# Processor.net
KiCad netlist of a schematic drawn in Altium Designer
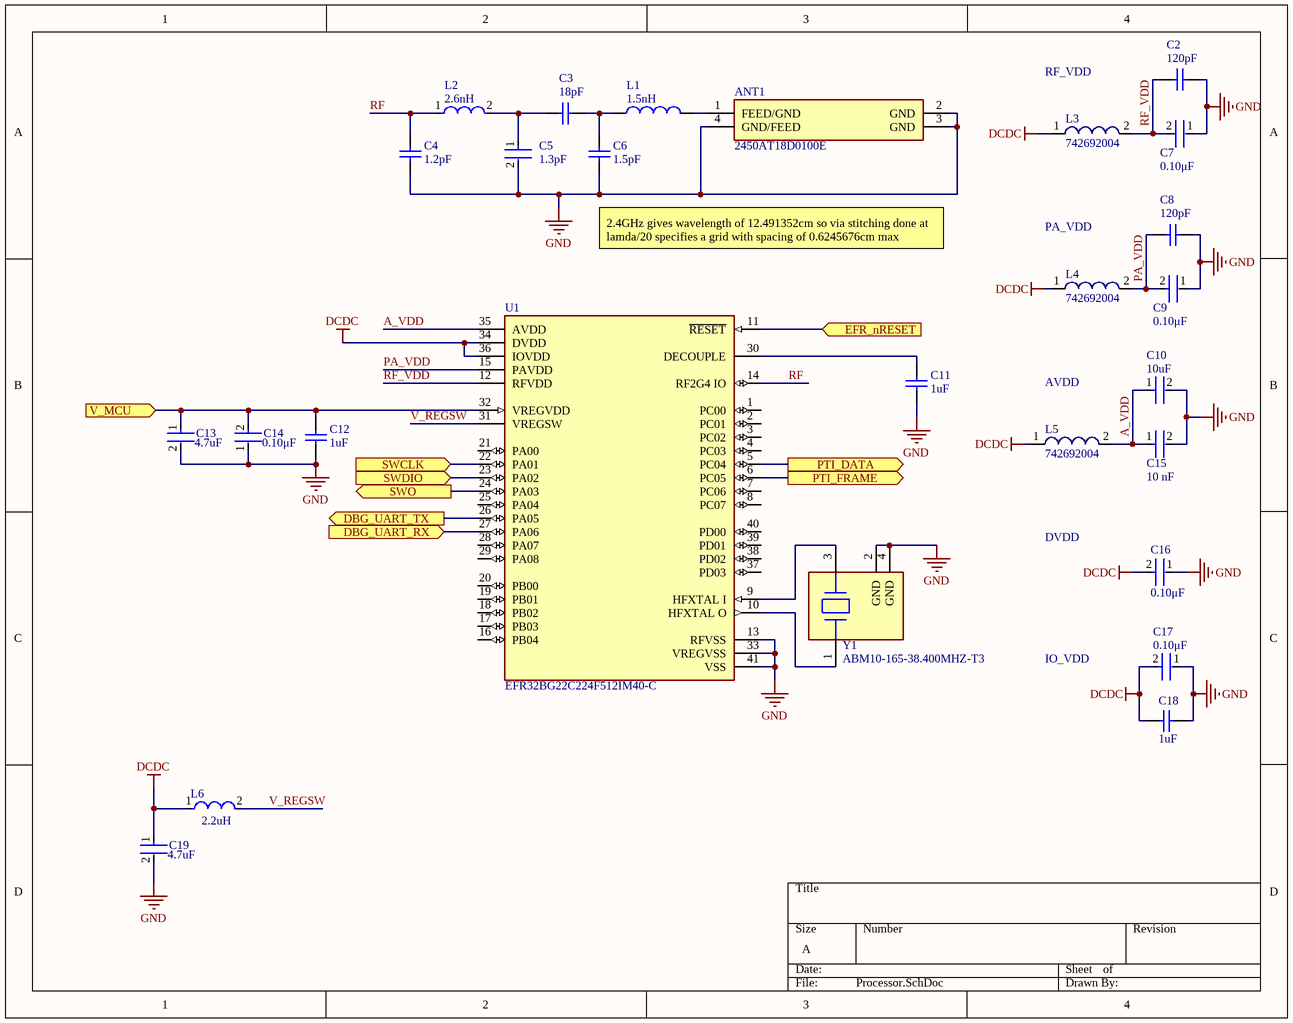
[diagram p0: Processor.SchDoc]

(export (version "E")
  (design (tool "Eeschema 10.0.6"))
  (components
    (comp (ref "ANT1")
      (value "2450AT18D0100E")
      (footprint "FP-2450AT18D0100E-MFG")
      (description "RF ANT 2.4GHZ CHIP SOLDER SMD")
      (libsource (lib "Altium Content Vault") (part "2754107183b9f3d7969499aeff111fc"))
    )
    (comp (ref "C2")
      (value "C0603C121J5GACAUTO")
      (footprint "CAPC1608X87X35LL15T15")
      (fields (field (name "MANUFACTURER") "Kemet") (field (name "CAPACITANCE") "120pF"))
      (libsource (lib "Altium Content Vault") (part "CAP"))
    )
    (comp (ref "C3")
      (value "0402ZK180GBSTR")
      (footprint "CAPC1006X50X20NL10T10")
      (fields (field (name "MANUFACTURER") "AVX Interconnect / Elco") (field (name "CAPACITANCE") "18pF"))
      (libsource (lib "Altium Content Vault") (part "CAP"))
    )
    (comp (ref "C4")
      (value "04023J1R2BBSTR")
      (footprint "CAPC1006X50X20LL10T10")
      (fields (field (name "MANUFACTURER") "AVX Interconnect / Elco") (field (name "CAPACITANCE") "1.2pF"))
      (libsource (lib "Altium Content Vault") (part "CAP"))
    )
    (comp (ref "C5")
      (value "GJM1555C1H1R3BB01D")
      (footprint "FP-GJM155-0_05-MFG")
      (description "Multi-Layer Ceramic Capacitor 1.3pF C0G  ±0.1pF 0402 Paper T/R")
      (fields (field (name "CAPACITANCE") "1.3pF"))
      (libsource (lib "Altium Content Vault") (part "02cd4be3c70576c341d710602a673aa"))
    )
    (comp (ref "C6")
      (value "04023J1R5PBSTR")
      (footprint "CAPC1006X50X20ML10T10")
      (fields (field (name "MANUFACTURER") "AVX Interconnect / Elco") (field (name "CAPACITANCE") "1.5pF"))
      (libsource (lib "Altium Content Vault") (part "CAP"))
    )
    (comp (ref "C7")
      (value "GRM155R71C104KA88D")
      (footprint "FP-GRM15-MFG")
      (description "CAP CER 0.1UF 16V X7R 0402")
      (fields
        (field (name "TOLERANCE") "10%")
        (field (name "OCTOPART") "https://octopart.com/grm155r71c104ka88d-murata-196880")
        (field (name "CAPACITANCE") "0.10μF")
      )
      (libsource (lib "Altium Content Vault") (part "236180d848d6139a670b325ea6854c9"))
    )
    (comp (ref "C8")
      (value "C0603C121J5GACAUTO")
      (footprint "CAPC1608X87X35LL15T15")
      (fields (field (name "MANUFACTURER") "Kemet") (field (name "CAPACITANCE") "120pF"))
      (libsource (lib "Altium Content Vault") (part "CAP"))
    )
    (comp (ref "C9")
      (value "GRM155R71C104KA88D")
      (footprint "FP-GRM15-MFG")
      (description "CAP CER 0.1UF 16V X7R 0402")
      (fields
        (field (name "TOLERANCE") "10%")
        (field (name "OCTOPART") "https://octopart.com/grm155r71c104ka88d-murata-196880")
        (field (name "CAPACITANCE") "0.10μF")
      )
      (libsource (lib "Altium Content Vault") (part "236180d848d6139a670b325ea6854c9"))
    )
    (comp (ref "C10")
      (value "GRM188R60J106ME47D")
      (footprint "FP-GRM188-0_1-e0_2_0_55-IPC_A")
      (description "Chip Multilayer Ceramic Capacitors for General Purpose, 0603, 10uF, X5R, 15%, 20%, 6.3V")
      (fields
        (field (name "CAPACITANCE") "10uF")
        (field (name "VOLTAGE") "6.3V")
        (field (name "TOLERANCE") "20%")
      )
      (libsource (lib "Altium Content Vault") (part "02cd4be3c70576c341d710602a673aa"))
    )
    (comp (ref "C11")
      (value "C0603C105K9PACTU")
      (footprint "CAPC1608X90X35LL15T15")
      (fields (field (name "MANUFACTURER") "Kemet") (field (name "CAPACITANCE") "1uF"))
      (libsource (lib "Altium Content Vault") (part "CAP"))
    )
    (comp (ref "C12")
      (value "C0603C105K9PACTU")
      (footprint "CAPC1608X90X35LL15T15")
      (fields (field (name "MANUFACTURER") "Kemet") (field (name "CAPACITANCE") "1uF"))
      (libsource (lib "Altium Content Vault") (part "CAP"))
    )
    (comp (ref "C13")
      (value "CL10B475KQ8NQNC")
      (footprint "FP-CL10-IPC_C")
      (description "CAP CER 4.7UF 6.3V X7R 0603")
      (fields
        (field (name "TOLERANCE") "10%")
        (field (name "CAPACITANCE") "4.7uF")
        (field (name "OCTOPART") "https://octopart.com/cl10b475kq8nqnc-samsung-24957976")
      )
      (libsource (lib "Altium Content Vault") (part "11868f565c42a9108669ba33697ecf6"))
    )
    (comp (ref "C14")
      (value "GRM155R71C104KA88D")
      (footprint "FP-GRM15-MFG")
      (description "CAP CER 0.1UF 16V X7R 0402")
      (fields
        (field (name "TOLERANCE") "10%")
        (field (name "OCTOPART") "https://octopart.com/grm155r71c104ka88d-murata-196880")
        (field (name "CAPACITANCE") "0.10μF")
      )
      (libsource (lib "Altium Content Vault") (part "236180d848d6139a670b325ea6854c9"))
    )
    (comp (ref "C15")
      (value "CC0603KRX7R9BB103")
      (footprint "FP-CC0603-DA-MFG")
      (description "CAP CER 10000PF 50V X7R 0603")
      (fields
        (field (name "TOLERANCE") "0.1")
        (field (name "MANUFACTURER") "YAGEO")
        (field (name "CAPACITANCE") "10 nF")
      )
      (libsource (lib "Altium Content Vault") (part "11868f565c42a9108669ba33697ecf6"))
    )
    (comp (ref "C16")
      (value "GRM155R71C104KA88D")
      (footprint "FP-GRM15-MFG")
      (description "CAP CER 0.1UF 16V X7R 0402")
      (fields
        (field (name "TOLERANCE") "10%")
        (field (name "OCTOPART") "https://octopart.com/grm155r71c104ka88d-murata-196880")
        (field (name "CAPACITANCE") "0.10μF")
      )
      (libsource (lib "Altium Content Vault") (part "236180d848d6139a670b325ea6854c9"))
    )
    (comp (ref "C17")
      (value "GRM155R71C104KA88D")
      (footprint "FP-GRM15-MFG")
      (description "CAP CER 0.1UF 16V X7R 0402")
      (fields
        (field (name "TOLERANCE") "10%")
        (field (name "OCTOPART") "https://octopart.com/grm155r71c104ka88d-murata-196880")
        (field (name "CAPACITANCE") "0.10μF")
      )
      (libsource (lib "Altium Content Vault") (part "236180d848d6139a670b325ea6854c9"))
    )
    (comp (ref "C18")
      (value "C0603C105K9PACTU")
      (footprint "CAPC1608X90X35LL15T15")
      (fields (field (name "MANUFACTURER") "Kemet") (field (name "CAPACITANCE") "1uF"))
      (libsource (lib "Altium Content Vault") (part "CAP"))
    )
    (comp (ref "C19")
      (value "CL10B475KQ8NQNC")
      (footprint "FP-CL10-IPC_C")
      (description "CAP CER 4.7UF 6.3V X7R 0603")
      (fields
        (field (name "TOLERANCE") "10%")
        (field (name "CAPACITANCE") "4.7uF")
        (field (name "OCTOPART") "https://octopart.com/cl10b475kq8nqnc-samsung-24957976")
      )
      (libsource (lib "Altium Content Vault") (part "11868f565c42a9108669ba33697ecf6"))
    )
    (comp (ref "L1")
      (value "744901015")
      (footprint "WE-TCI_0402")
      (description "744901015 Fixed Ind 1.5NH 700MA 200MOHM Sm")
      (fields (field (name "INDUCTANCE") "1.5nH"))
      (libsource (lib "Altium Content Vault") (part "Inductor - 1"))
    )
    (comp (ref "L2")
      (value "LQW15AN2N6G8ZD")
      (footprint "FP-LQW15AN_80-MFG")
      (description "Wire Wound RF Inductor for Automotive 2.6nH ±2% 1950mA 0.035Ω 0402 (1005)")
      (fields (field (name "INDUCTANCE") "2.6nH"))
      (libsource (lib "Altium Content Vault") (part "725321dda6339637d4d059423bc1c3c"))
    )
    (comp (ref "L3")
      (value "742692004")
      (footprint "WE-TMSB 0201")
      (description "Tiny Multilayer Suppression  Bead  WE-TMSB, Z= 240 Ohm")
      (fields (field (name "MANUFACTURER") "Wuerth Elektronik"))
      (libsource (lib "Altium Content Vault") (part "WE-IND-INDUCTOR-2"))
    )
    (comp (ref "L4")
      (value "742692004")
      (footprint "WE-TMSB 0201")
      (description "Tiny Multilayer Suppression  Bead  WE-TMSB, Z= 240 Ohm")
      (fields (field (name "MANUFACTURER") "Wuerth Elektronik"))
      (libsource (lib "Altium Content Vault") (part "WE-IND-INDUCTOR-2"))
    )
    (comp (ref "L5")
      (value "742692004")
      (footprint "WE-TMSB 0201")
      (description "Tiny Multilayer Suppression  Bead  WE-TMSB, Z= 240 Ohm")
      (fields (field (name "MANUFACTURER") "Wuerth Elektronik"))
      (libsource (lib "Altium Content Vault") (part "WE-IND-INDUCTOR-2"))
    )
    (comp (ref "L6")
      (value "LQM18PZ2R2MFHD")
      (footprint "FP-LQM18PZ_FH-MFG")
      (description "FIXED IND 2.2UH 700MA 470MOHM SM")
      (fields (field (name "TOLERANCE") "20%") (field (name "INDUCTANCE") "2.2uH"))
      (libsource (lib "Altium Content Vault") (part "725321dda6339637d4d059423bc1c3c"))
    )
    (comp (ref "U1")
      (value "EFR32BG22C224F512IM40-C")
      (footprint "FP-EFR32BG22C224F512IM40-IPC_C")
      (description "BLUE GECKO, QFN40, SECURE BOOT W")
      (libsource (lib "Altium Content Vault") (part "033e3ed7e9e35dc86ce331788b84acd"))
    )
    (comp (ref "Y1")
      (value "ABM10-165-38.400MHZ-T3")
      (footprint "FP-ABM10-165-MFG")
      (description "CRYSTAL 38.4000MHZ 10PF SMD")
      (libsource (lib "Altium Content Vault") (part "bb957c91121ec8fefe2b6ffeb011d4b"))
    )
  )
  (nets
    (net (code "1") (name "/A_VDD") (class "Default")
      (node (ref "C10") (pin "1") (pinfunction "1_1") (pintype "passive"))
      (node (ref "C15") (pin "1") (pinfunction "1_1") (pintype "passive"))
      (node (ref "L5") (pin "2") (pinfunction "2_2") (pintype "passive"))
      (node (ref "U1") (pin "35") (pinfunction "AVDD_35") (pintype "power_in"))
    )
    (net (code "2") (name "/DBG_UART_RX") (class "Default")
      (node (ref "U1") (pin "27") (pinfunction "PA06_27") (pintype "bidirectional"))
    )
    (net (code "3") (name "/DBG_UART_TX") (class "Default")
      (node (ref "U1") (pin "26") (pinfunction "PA05_26") (pintype "bidirectional"))
    )
    (net (code "4") (name "/EFR_nRESET") (class "Default")
      (node (ref "U1") (pin "11") (pinfunction "~{RESET}_11") (pintype "input"))
    )
    (net (code "5") (name "/PA_VDD") (class "Default")
      (node (ref "C8") (pin "1") (pinfunction "1_1") (pintype "passive"))
      (node (ref "C9") (pin "2") (pinfunction "2_2") (pintype "passive"))
      (node (ref "L4") (pin "2") (pinfunction "2_2") (pintype "passive"))
      (node (ref "U1") (pin "15") (pinfunction "PAVDD_15") (pintype "power_in"))
    )
    (net (code "6") (name "/PTI_DATA") (class "Default")
      (node (ref "U1") (pin "5") (pinfunction "PC04_5") (pintype "bidirectional"))
    )
    (net (code "7") (name "/PTI_FRAME") (class "Default")
      (node (ref "U1") (pin "6") (pinfunction "PC05_6") (pintype "bidirectional"))
    )
    (net (code "8") (name "/RF") (class "Default")
      (node (ref "C4") (pin "2") (pinfunction "2_2") (pintype "passive"))
      (node (ref "L2") (pin "1") (pinfunction "1_1") (pintype "passive"))
      (node (ref "U1") (pin "14") (pinfunction "RF2G4_IO_14") (pintype "bidirectional"))
    )
    (net (code "9") (name "/RF_VDD") (class "Default")
      (node (ref "C2") (pin "1") (pinfunction "1_1") (pintype "passive"))
      (node (ref "C7") (pin "2") (pinfunction "2_2") (pintype "passive"))
      (node (ref "L3") (pin "2") (pinfunction "2_2") (pintype "passive"))
      (node (ref "U1") (pin "12") (pinfunction "RFVDD_12") (pintype "power_in"))
    )
    (net (code "10") (name "/SWCLK") (class "Default")
      (node (ref "U1") (pin "22") (pinfunction "PA01_22") (pintype "bidirectional"))
    )
    (net (code "11") (name "/SWDIO") (class "Default")
      (node (ref "U1") (pin "23") (pinfunction "PA02_23") (pintype "bidirectional"))
    )
    (net (code "12") (name "/SWO") (class "Default")
      (node (ref "U1") (pin "24") (pinfunction "PA03_24") (pintype "bidirectional"))
    )
    (net (code "13") (name "/V_MCU") (class "Default")
      (node (ref "C12") (pin "2") (pinfunction "2_2") (pintype "passive"))
      (node (ref "C13") (pin "1") (pinfunction "1_1") (pintype "passive"))
      (node (ref "C14") (pin "2") (pinfunction "2_2") (pintype "passive"))
      (node (ref "U1") (pin "32") (pinfunction "VREGVDD_32") (pintype "input"))
    )
    (net (code "14") (name "/V_REGSW") (class "Default")
      (node (ref "L6") (pin "2") (pinfunction "2_2") (pintype "passive"))
      (node (ref "U1") (pin "31") (pinfunction "VREGSW_31") (pintype "power_in"))
    )
    (net (code "15") (name "DCDC") (class "Default")
      (node (ref "C16") (pin "2") (pinfunction "2_2") (pintype "passive"))
      (node (ref "C17") (pin "2") (pinfunction "2_2") (pintype "passive"))
      (node (ref "C18") (pin "2") (pinfunction "2_2") (pintype "passive"))
      (node (ref "C19") (pin "1") (pinfunction "1_1") (pintype "passive"))
      (node (ref "L3") (pin "1") (pinfunction "1_1") (pintype "passive"))
      (node (ref "L4") (pin "1") (pinfunction "1_1") (pintype "passive"))
      (node (ref "L5") (pin "1") (pinfunction "1_1") (pintype "passive"))
      (node (ref "L6") (pin "1") (pinfunction "1_1") (pintype "passive"))
      (node (ref "U1") (pin "34") (pinfunction "DVDD_34") (pintype "power_in"))
      (node (ref "U1") (pin "36") (pinfunction "IOVDD_36") (pintype "power_in"))
    )
    (net (code "16") (name "GND") (class "Default")
      (node (ref "ANT1") (pin "2") (pinfunction "GND_2") (pintype "power_in"))
      (node (ref "ANT1") (pin "3") (pinfunction "GND_3") (pintype "power_in"))
      (node (ref "ANT1") (pin "4") (pinfunction "GND/FEED_4") (pintype "power_in"))
      (node (ref "C10") (pin "2") (pinfunction "2_2") (pintype "passive"))
      (node (ref "C11") (pin "1") (pinfunction "1_1") (pintype "passive"))
      (node (ref "C12") (pin "1") (pinfunction "1_1") (pintype "passive"))
      (node (ref "C13") (pin "2") (pinfunction "2_2") (pintype "passive"))
      (node (ref "C14") (pin "1") (pinfunction "1_1") (pintype "passive"))
      (node (ref "C15") (pin "2") (pinfunction "2_2") (pintype "passive"))
      (node (ref "C16") (pin "1") (pinfunction "1_1") (pintype "passive"))
      (node (ref "C17") (pin "1") (pinfunction "1_1") (pintype "passive"))
      (node (ref "C18") (pin "1") (pinfunction "1_1") (pintype "passive"))
      (node (ref "C19") (pin "2") (pinfunction "2_2") (pintype "passive"))
      (node (ref "C2") (pin "2") (pinfunction "2_2") (pintype "passive"))
      (node (ref "C4") (pin "1") (pinfunction "1_1") (pintype "passive"))
      (node (ref "C5") (pin "2") (pinfunction "2_2") (pintype "passive"))
      (node (ref "C6") (pin "1") (pinfunction "1_1") (pintype "passive"))
      (node (ref "C7") (pin "1") (pinfunction "1_1") (pintype "passive"))
      (node (ref "C8") (pin "2") (pinfunction "2_2") (pintype "passive"))
      (node (ref "C9") (pin "1") (pinfunction "1_1") (pintype "passive"))
      (node (ref "U1") (pin "13") (pinfunction "RFVSS_13") (pintype "power_in"))
      (node (ref "U1") (pin "33") (pinfunction "VREGVSS_33") (pintype "power_in"))
      (node (ref "U1") (pin "41") (pinfunction "VSS_41") (pintype "power_in"))
      (node (ref "Y1") (pin "2") (pinfunction "GND_2") (pintype "power_in"))
      (node (ref "Y1") (pin "4") (pinfunction "GND_4") (pintype "power_in"))
    )
    (net (code "17") (name "Net-(ANT1-FEED{slash}GND)") (class "Default")
      (node (ref "ANT1") (pin "1") (pinfunction "FEED/GND_1") (pintype "power_in"))
      (node (ref "L1") (pin "2") (pinfunction "2_2") (pintype "passive"))
    )
    (net (code "18") (name "Net-(C3-Pad1)") (class "Default")
      (node (ref "C3") (pin "1") (pinfunction "1_1") (pintype "passive"))
      (node (ref "C5") (pin "1") (pinfunction "1_1") (pintype "passive"))
      (node (ref "L2") (pin "2") (pinfunction "2_2") (pintype "passive"))
    )
    (net (code "19") (name "Net-(C3-Pad2)") (class "Default")
      (node (ref "C3") (pin "2") (pinfunction "2_2") (pintype "passive"))
      (node (ref "C6") (pin "2") (pinfunction "2_2") (pintype "passive"))
      (node (ref "L1") (pin "1") (pinfunction "1_1") (pintype "passive"))
    )
    (net (code "20") (name "Net-(U1-DECOUPLE)") (class "Default")
      (node (ref "C11") (pin "2") (pinfunction "2_2") (pintype "passive"))
      (node (ref "U1") (pin "30") (pinfunction "DECOUPLE_30") (pintype "passive"))
    )
    (net (code "21") (name "Net-(U1-HFXTAL_I)") (class "Default")
      (node (ref "U1") (pin "9") (pinfunction "HFXTAL_I_9") (pintype "input"))
      (node (ref "Y1") (pin "3") (pinfunction "2_Crystal_3") (pintype "passive"))
    )
    (net (code "22") (name "Net-(U1-HFXTAL_O)") (class "Default")
      (node (ref "U1") (pin "10") (pinfunction "HFXTAL_O_10") (pintype "output"))
      (node (ref "Y1") (pin "1") (pinfunction "1_Crystal_1") (pintype "passive"))
    )
    (net (code "23") (name "unconnected-(U1-PA00-Pad21)") (class "Default")
      (node (ref "U1") (pin "21") (pinfunction "PA00_21") (pintype "bidirectional"))
    )
    (net (code "24") (name "unconnected-(U1-PA04-Pad25)") (class "Default")
      (node (ref "U1") (pin "25") (pinfunction "PA04_25") (pintype "bidirectional"))
    )
    (net (code "25") (name "unconnected-(U1-PA07-Pad28)") (class "Default")
      (node (ref "U1") (pin "28") (pinfunction "PA07_28") (pintype "bidirectional"))
    )
    (net (code "26") (name "unconnected-(U1-PA08-Pad29)") (class "Default")
      (node (ref "U1") (pin "29") (pinfunction "PA08_29") (pintype "bidirectional"))
    )
    (net (code "27") (name "unconnected-(U1-PB00-Pad20)") (class "Default")
      (node (ref "U1") (pin "20") (pinfunction "PB00_20") (pintype "bidirectional"))
    )
    (net (code "28") (name "unconnected-(U1-PB01-Pad19)") (class "Default")
      (node (ref "U1") (pin "19") (pinfunction "PB01_19") (pintype "bidirectional"))
    )
    (net (code "29") (name "unconnected-(U1-PB02-Pad18)") (class "Default")
      (node (ref "U1") (pin "18") (pinfunction "PB02_18") (pintype "bidirectional"))
    )
    (net (code "30") (name "unconnected-(U1-PB03-Pad17)") (class "Default")
      (node (ref "U1") (pin "17") (pinfunction "PB03_17") (pintype "bidirectional"))
    )
    (net (code "31") (name "unconnected-(U1-PB04-Pad16)") (class "Default")
      (node (ref "U1") (pin "16") (pinfunction "PB04_16") (pintype "bidirectional"))
    )
    (net (code "32") (name "unconnected-(U1-PC00-Pad1)") (class "Default")
      (node (ref "U1") (pin "1") (pinfunction "PC00_1") (pintype "bidirectional"))
    )
    (net (code "33") (name "unconnected-(U1-PC01-Pad2)") (class "Default")
      (node (ref "U1") (pin "2") (pinfunction "PC01_2") (pintype "bidirectional"))
    )
    (net (code "34") (name "unconnected-(U1-PC02-Pad3)") (class "Default")
      (node (ref "U1") (pin "3") (pinfunction "PC02_3") (pintype "bidirectional"))
    )
    (net (code "35") (name "unconnected-(U1-PC03-Pad4)") (class "Default")
      (node (ref "U1") (pin "4") (pinfunction "PC03_4") (pintype "bidirectional"))
    )
    (net (code "36") (name "unconnected-(U1-PC06-Pad7)") (class "Default")
      (node (ref "U1") (pin "7") (pinfunction "PC06_7") (pintype "bidirectional"))
    )
    (net (code "37") (name "unconnected-(U1-PC07-Pad8)") (class "Default")
      (node (ref "U1") (pin "8") (pinfunction "PC07_8") (pintype "bidirectional"))
    )
    (net (code "38") (name "unconnected-(U1-PD00-Pad40)") (class "Default")
      (node (ref "U1") (pin "40") (pinfunction "PD00_40") (pintype "bidirectional"))
    )
    (net (code "39") (name "unconnected-(U1-PD01-Pad39)") (class "Default")
      (node (ref "U1") (pin "39") (pinfunction "PD01_39") (pintype "bidirectional"))
    )
    (net (code "40") (name "unconnected-(U1-PD02-Pad38)") (class "Default")
      (node (ref "U1") (pin "38") (pinfunction "PD02_38") (pintype "bidirectional"))
    )
    (net (code "41") (name "unconnected-(U1-PD03-Pad37)") (class "Default")
      (node (ref "U1") (pin "37") (pinfunction "PD03_37") (pintype "bidirectional"))
    )
  )
)
